# XP-Hardv.net
KiCad netlist of a schematic drawn in Altium Designer
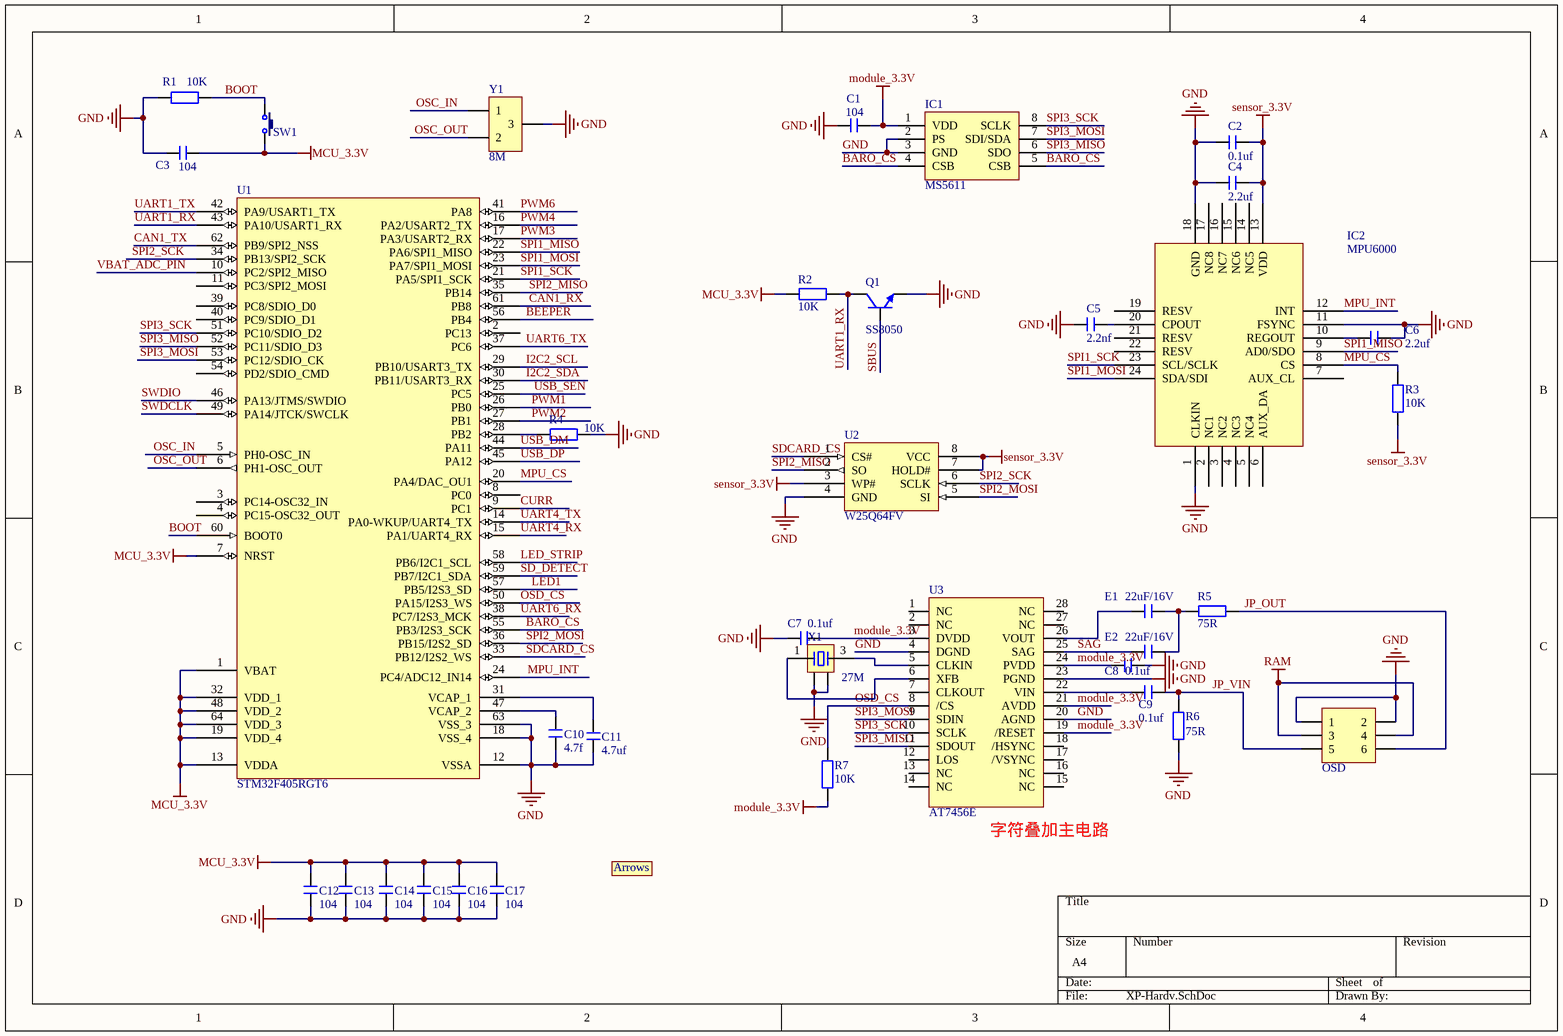
[diagram p0: XP-Hardv.SchDoc]

(export (version "E")
  (design (tool "Eeschema 10.0.6"))
  (components
    (comp (ref "C1")
      (value "104")
      (footprint "C 0402_M")
      (description "无极性贴片电容")
      (fields (field (name "版权归属") "源创客"))
      (libsource (lib "3.1   - 电阻-电容-电感") (part "C"))
    )
    (comp (ref "C2")
      (value "0.1uf")
      (footprint "C 0402_M")
      (description "无极性贴片电容")
      (fields (field (name "版权归属") "源创客"))
      (libsource (lib "3.1   - 电阻-电容-电感") (part "C"))
    )
    (comp (ref "C3")
      (value "104")
      (footprint "C 0402_M")
      (description "无极性贴片电容")
      (fields (field (name "版权归属") "源创客"))
      (libsource (lib "3.1   - 电阻-电容-电感") (part "C"))
    )
    (comp (ref "C4")
      (value "2.2uf")
      (footprint "C 0402_M")
      (description "无极性贴片电容")
      (fields (field (name "版权归属") "源创客"))
      (libsource (lib "3.1   - 电阻-电容-电感") (part "C"))
    )
    (comp (ref "C5")
      (value "2.2nf")
      (footprint "C 0402_M")
      (description "无极性贴片电容")
      (fields (field (name "版权归属") "源创客"))
      (libsource (lib "3.1   - 电阻-电容-电感") (part "C"))
    )
    (comp (ref "C6")
      (value "2.2uf")
      (footprint "C 0402_M")
      (description "无极性贴片电容")
      (fields (field (name "版权归属") "源创客"))
      (libsource (lib "3.1   - 电阻-电容-电感") (part "C"))
    )
    (comp (ref "C7")
      (value "0.1uf")
      (footprint "C 0402_M")
      (description "无极性贴片电容")
      (fields (field (name "版权归属") "源创客"))
      (libsource (lib "3.1   - 电阻-电容-电感") (part "C"))
    )
    (comp (ref "C8")
      (value "0.1uf")
      (footprint "C 0402_M")
      (description "无极性贴片电容")
      (fields (field (name "版权归属") "源创客"))
      (libsource (lib "3.1   - 电阻-电容-电感") (part "C"))
    )
    (comp (ref "C9")
      (value "0.1uf")
      (footprint "C 0402_M")
      (description "无极性贴片电容")
      (fields (field (name "版权归属") "源创客"))
      (libsource (lib "3.1   - 电阻-电容-电感") (part "C"))
    )
    (comp (ref "C10")
      (value "4.7f")
      (footprint "C 0402_M")
      (description "无极性贴片电容")
      (fields (field (name "版权归属") "源创客"))
      (libsource (lib "3.1   - 电阻-电容-电感") (part "C"))
    )
    (comp (ref "C11")
      (value "4.7uf")
      (footprint "C 0402_M")
      (description "无极性贴片电容")
      (fields (field (name "版权归属") "源创客"))
      (libsource (lib "3.1   - 电阻-电容-电感") (part "C"))
    )
    (comp (ref "C12")
      (value "104")
      (footprint "C 0402_M")
      (description "无极性贴片电容")
      (fields (field (name "版权归属") "源创客"))
      (libsource (lib "3.1   - 电阻-电容-电感") (part "C"))
    )
    (comp (ref "C13")
      (value "104")
      (footprint "C 0402_M")
      (description "无极性贴片电容")
      (fields (field (name "版权归属") "源创客"))
      (libsource (lib "3.1   - 电阻-电容-电感") (part "C"))
    )
    (comp (ref "C14")
      (value "104")
      (footprint "C 0402_M")
      (description "无极性贴片电容")
      (fields (field (name "版权归属") "源创客"))
      (libsource (lib "3.1   - 电阻-电容-电感") (part "C"))
    )
    (comp (ref "C15")
      (value "104")
      (footprint "C 0402_M")
      (description "无极性贴片电容")
      (fields (field (name "版权归属") "源创客"))
      (libsource (lib "3.1   - 电阻-电容-电感") (part "C"))
    )
    (comp (ref "C16")
      (value "104")
      (footprint "C 0402_M")
      (description "无极性贴片电容")
      (fields (field (name "版权归属") "源创客"))
      (libsource (lib "3.1   - 电阻-电容-电感") (part "C"))
    )
    (comp (ref "C17")
      (value "104")
      (footprint "C 0402_M")
      (description "无极性贴片电容")
      (fields (field (name "版权归属") "源创客"))
      (libsource (lib "3.1   - 电阻-电容-电感") (part "C"))
    )
    (comp (ref "E1")
      (value "22uF/16V")
      (footprint "C 0805_L")
      (description "无极性贴片电容")
      (fields (field (name "版权归属") "源创客"))
      (libsource (lib "3.1   - 电阻-电容-电感") (part "C"))
    )
    (comp (ref "E2")
      (value "22uF/16V")
      (footprint "C 0805_L")
      (description "无极性贴片电容")
      (fields (field (name "版权归属") "源创客"))
      (libsource (lib "3.1   - 电阻-电容-电感") (part "C"))
    )
    (comp (ref "IC1")
      (value "MS5611")
      (footprint "MS5611")
      (description "气压传感器")
      (fields (field (name "版权归属") "源创客"))
      (libsource (lib "11.1 - 传感元件") (part "MS5611"))
    )
    (comp (ref "IC2")
      (value "MPU6000")
      (footprint "MPU6050")
      (fields (field (name "版权所有") "河池学院智能控制重点实验室"))
      (libsource (lib "传感器件") (part "MPU6000"))
    )
    (comp (ref "logo1")
      (value "Arrows")
      (footprint "Arrows - E")
      (fields (field (name "版权所有") "深圳市哈鸣科技有限公司"))
      (libsource (lib "BETAFPV") (part "Arrows"))
    )
    (comp (ref "OSD")
      (value "Header3X2")
      (footprint "PHD2.0-LI-2x3P")
      (description "3*2P接插件")
      (fields (field (name "版权归属") "源创客"))
      (libsource (lib "4.4   - 接插件-脚距2.0") (part "Header 3X2"))
    )
    (comp (ref "Q1")
      (value "SS8050")
      (footprint "SOT23-3M")
      (description "高频放大-NPN型")
      (fields (field (name "版权归属") "源创客"))
      (libsource (lib "6.2   - 三极管") (part "8050-SMD"))
    )
    (comp (ref "R1")
      (value "10K")
      (footprint "R 0402_M")
      (description "贴片电阻")
      (fields (field (name "版权归属") "源创客"))
      (libsource (lib "3.1   - 电阻-电容-电感") (part "R"))
    )
    (comp (ref "R2")
      (value "10K")
      (footprint "R 0402_M")
      (description "贴片电阻")
      (fields (field (name "版权归属") "源创客"))
      (libsource (lib "3.1   - 电阻-电容-电感") (part "R"))
    )
    (comp (ref "R3")
      (value "10K")
      (footprint "R 0402_M")
      (description "贴片电阻")
      (fields (field (name "版权归属") "源创客"))
      (libsource (lib "3.1   - 电阻-电容-电感") (part "R"))
    )
    (comp (ref "R4")
      (value "10K")
      (footprint "R 0402_M")
      (description "贴片电阻")
      (fields (field (name "版权归属") "源创客"))
      (libsource (lib "3.1   - 电阻-电容-电感") (part "R"))
    )
    (comp (ref "R5")
      (value "75R")
      (footprint "R 0402_M")
      (description "贴片电阻")
      (fields (field (name "版权归属") "源创客"))
      (libsource (lib "3.1   - 电阻-电容-电感") (part "R"))
    )
    (comp (ref "R6")
      (value "75R")
      (footprint "R 0402_M")
      (description "贴片电阻")
      (fields (field (name "版权归属") "源创客"))
      (libsource (lib "3.1   - 电阻-电容-电感") (part "R"))
    )
    (comp (ref "R7")
      (value "10K")
      (footprint "R 0402_M")
      (description "贴片电阻")
      (fields (field (name "版权归属") "源创客"))
      (libsource (lib "3.1   - 电阻-电容-电感") (part "R"))
    )
    (comp (ref "SW1")
      (value "3x6x5")
      (footprint "TSW 3*6*4.3-S-W")
      (description "3x6轻触开关")
      (fields (field (name "版权归属") "源创客"))
      (libsource (lib "5.1   - 按键-开关") (part "TSW 3x6"))
    )
    (comp (ref "U1")
      (value "STM32F405RGT6")
      (footprint "LQFP64 10x10_N")
      (description "32位STM单片机")
      (libsource (lib "2.1   - STM32系列单片机") (part "STM32F405RGT6"))
    )
    (comp (ref "U2")
      (value "W25Q64FV")
      (footprint "Q-WSON8_6x5")
      (description "存储器芯片-64M")
      (libsource (lib "L-存储器芯片") (part "W25Q64FV"))
    )
    (comp (ref "U3")
      (value "AT7456E")
      (footprint "AT7456E - B")
      (fields (field (name "LIBRARY NAME") "字符叠加芯片") (field (name "版权所有") "河池学院智能控制重点实验室"))
      (libsource (lib "L-AT7456E") (part "AT7456E"))
    )
    (comp (ref "X1")
      (value "27M")
      (footprint "OSC 3225-4P")
      (description "4脚无源晶振")
      (fields (field (name "版权归属") "源创客"))
      (libsource (lib "10.1 - 保险丝-晶振") (part "XTAL-4P"))
    )
    (comp (ref "Y1")
      (value "8M")
      (footprint "L - CSTCE-3213")
      (fields (field (name "版权归属") "Ly"))
      (libsource (lib "L-晶振") (part "CSTCE"))
    )
  )
  (nets
    (net (code "1") (name "/BARO_CS") (class "Default")
      (node (ref "IC1") (pin "4") (pinfunction "CSB_4") (pintype "passive"))
      (node (ref "IC1") (pin "5") (pinfunction "CSB_5") (pintype "passive"))
      (node (ref "U1") (pin "55") (pinfunction "PB3/I2S3_SCK_55") (pintype "bidirectional"))
    )
    (net (code "2") (name "/BEEPER") (class "Default")
      (node (ref "U1") (pin "56") (pinfunction "PB4_56") (pintype "bidirectional"))
    )
    (net (code "3") (name "/BOOT") (class "Default")
      (node (ref "R1") (pin "1") (pinfunction "1_1") (pintype "passive"))
      (node (ref "SW1") (pin "1") (pinfunction "1_1") (pintype "passive"))
      (node (ref "U1") (pin "60") (pinfunction "BOOT0_60") (pintype "input"))
    )
    (net (code "4") (name "/CAN1_RX") (class "Default")
      (node (ref "U1") (pin "61") (pinfunction "PB8_61") (pintype "bidirectional"))
    )
    (net (code "5") (name "/CAN1_TX") (class "Default")
      (node (ref "U1") (pin "62") (pinfunction "PB9/SPI2_NSS_62") (pintype "bidirectional"))
    )
    (net (code "6") (name "/CURR") (class "Default")
      (node (ref "U1") (pin "9") (pinfunction "PC1_9") (pintype "bidirectional"))
    )
    (net (code "7") (name "/I2C2_SCL") (class "Default")
      (node (ref "U1") (pin "29") (pinfunction "PB10/USART3_TX_29") (pintype "bidirectional"))
    )
    (net (code "8") (name "/I2C2_SDA") (class "Default")
      (node (ref "U1") (pin "30") (pinfunction "PB11/USART3_RX_30") (pintype "bidirectional"))
    )
    (net (code "9") (name "/JP_OUT") (class "Default")
      (node (ref "OSD") (pin "6") (pinfunction "6_6") (pintype "passive"))
      (node (ref "R5") (pin "2") (pinfunction "2_2") (pintype "passive"))
    )
    (net (code "10") (name "/JP_VIN") (class "Default")
      (node (ref "C9") (pin "2") (pinfunction "2_2") (pintype "passive"))
      (node (ref "OSD") (pin "5") (pinfunction "5_5") (pintype "passive"))
      (node (ref "R6") (pin "2") (pinfunction "2_2") (pintype "passive"))
    )
    (net (code "11") (name "/LED1") (class "Default")
      (node (ref "U1") (pin "57") (pinfunction "PB5/I2S3_SD_57") (pintype "bidirectional"))
    )
    (net (code "12") (name "/LED_STRIP") (class "Default")
      (node (ref "U1") (pin "58") (pinfunction "PB6/I2C1_SCL_58") (pintype "bidirectional"))
    )
    (net (code "13") (name "/MPU_CS") (class "Default")
      (node (ref "IC2") (pin "8") (pinfunction "CS_8") (pintype "passive"))
      (node (ref "R3") (pin "2") (pinfunction "2_2") (pintype "passive"))
      (node (ref "U1") (pin "20") (pinfunction "PA4/DAC_OU1_20") (pintype "bidirectional"))
    )
    (net (code "14") (name "/MPU_INT") (class "Default")
      (node (ref "IC2") (pin "12") (pinfunction "INT_12") (pintype "passive"))
      (node (ref "U1") (pin "24") (pinfunction "PC4/ADC12_IN14_24") (pintype "bidirectional"))
    )
    (net (code "15") (name "/OSC_IN") (class "Default")
      (node (ref "U1") (pin "5") (pinfunction "PH0-OSC_IN_5") (pintype "input"))
      (node (ref "Y1") (pin "1") (pinfunction "1_1") (pintype "passive"))
    )
    (net (code "16") (name "/OSC_OUT") (class "Default")
      (node (ref "U1") (pin "6") (pinfunction "PH1-OSC_OUT_6") (pintype "output"))
      (node (ref "Y1") (pin "2") (pinfunction "2_2") (pintype "passive"))
    )
    (net (code "17") (name "/OSD_CS") (class "Default")
      (node (ref "R7") (pin "2") (pinfunction "2_2") (pintype "passive"))
      (node (ref "U1") (pin "50") (pinfunction "PA15/I2S3_WS_50") (pintype "bidirectional"))
      (node (ref "U3") (pin "8") (pinfunction "/CS_8") (pintype "passive"))
    )
    (net (code "18") (name "/PWM1") (class "Default")
      (node (ref "U1") (pin "26") (pinfunction "PB0_26") (pintype "bidirectional"))
    )
    (net (code "19") (name "/PWM2") (class "Default")
      (node (ref "U1") (pin "27") (pinfunction "PB1_27") (pintype "bidirectional"))
    )
    (net (code "20") (name "/PWM3") (class "Default")
      (node (ref "U1") (pin "17") (pinfunction "PA3/USART2_RX_17") (pintype "bidirectional"))
    )
    (net (code "21") (name "/PWM4") (class "Default")
      (node (ref "U1") (pin "16") (pinfunction "PA2/USART2_TX_16") (pintype "bidirectional"))
    )
    (net (code "22") (name "/PWM6") (class "Default")
      (node (ref "U1") (pin "41") (pinfunction "PA8_41") (pintype "bidirectional"))
    )
    (net (code "23") (name "/SAG") (class "Default")
      (node (ref "E2") (pin "1") (pinfunction "1_1") (pintype "passive"))
      (node (ref "U3") (pin "25") (pinfunction "SAG_25") (pintype "passive"))
    )
    (net (code "24") (name "/SBUS") (class "Default")
      (node (ref "Q1") (pin "1") (pinfunction "B_1") (pintype "passive"))
    )
    (net (code "25") (name "/SDCARD_CS") (class "Default")
      (node (ref "U1") (pin "33") (pinfunction "PB12/I2S2_WS_33") (pintype "bidirectional"))
      (node (ref "U2") (pin "1") (pinfunction "CS#_1") (pintype "input"))
    )
    (net (code "26") (name "/SD_DETECT") (class "Default")
      (node (ref "U1") (pin "59") (pinfunction "PB7/I2C1_SDA_59") (pintype "bidirectional"))
    )
    (net (code "27") (name "/SPI1_MISO") (class "Default")
      (node (ref "IC2") (pin "9") (pinfunction "AD0/SDO_9") (pintype "passive"))
      (node (ref "U1") (pin "22") (pinfunction "PA6/SPI1_MISO_22") (pintype "bidirectional"))
    )
    (net (code "28") (name "/SPI1_MOSI") (class "Default")
      (node (ref "IC2") (pin "24") (pinfunction "SDA/SDI_24") (pintype "passive"))
      (node (ref "U1") (pin "23") (pinfunction "PA7/SPI1_MOSI_23") (pintype "bidirectional"))
    )
    (net (code "29") (name "/SPI1_SCK") (class "Default")
      (node (ref "IC2") (pin "23") (pinfunction "SCL/SCLK_23") (pintype "passive"))
      (node (ref "U1") (pin "21") (pinfunction "PA5/SPI1_SCK_21") (pintype "bidirectional"))
    )
    (net (code "30") (name "/SPI2_MISO") (class "Default")
      (node (ref "U1") (pin "35") (pinfunction "PB14_35") (pintype "bidirectional"))
      (node (ref "U2") (pin "2") (pinfunction "SO_2") (pintype "output"))
    )
    (net (code "31") (name "/SPI2_MOSI") (class "Default")
      (node (ref "U1") (pin "36") (pinfunction "PB15/I2S2_SD_36") (pintype "bidirectional"))
      (node (ref "U2") (pin "5") (pinfunction "SI_5") (pintype "input"))
    )
    (net (code "32") (name "/SPI2_SCK") (class "Default")
      (node (ref "U1") (pin "34") (pinfunction "PB13/SPI2_SCK_34") (pintype "bidirectional"))
      (node (ref "U2") (pin "6") (pinfunction "SCLK_6") (pintype "input"))
    )
    (net (code "33") (name "/SPI3_MISO") (class "Default")
      (node (ref "IC1") (pin "6") (pinfunction "SDO_6") (pintype "passive"))
      (node (ref "U1") (pin "52") (pinfunction "PC11/SDIO_D3_52") (pintype "bidirectional"))
      (node (ref "U3") (pin "11") (pinfunction "SDOUT_11") (pintype "passive"))
    )
    (net (code "34") (name "/SPI3_MOSI") (class "Default")
      (node (ref "IC1") (pin "7") (pinfunction "SDI/SDA_7") (pintype "passive"))
      (node (ref "U1") (pin "53") (pinfunction "PC12/SDIO_CK_53") (pintype "bidirectional"))
      (node (ref "U3") (pin "9") (pinfunction "SDIN_9") (pintype "passive"))
    )
    (net (code "35") (name "/SPI3_SCK") (class "Default")
      (node (ref "IC1") (pin "8") (pinfunction "SCLK_8") (pintype "passive"))
      (node (ref "U1") (pin "51") (pinfunction "PC10/SDIO_D2_51") (pintype "bidirectional"))
      (node (ref "U3") (pin "10") (pinfunction "SCLK_10") (pintype "passive"))
    )
    (net (code "36") (name "/SWDCLK") (class "Default")
      (node (ref "U1") (pin "49") (pinfunction "PA14/JTCK/SWCLK_49") (pintype "bidirectional"))
    )
    (net (code "37") (name "/SWDIO") (class "Default")
      (node (ref "U1") (pin "46") (pinfunction "PA13/JTMS/SWDIO_46") (pintype "bidirectional"))
    )
    (net (code "38") (name "/UART1_RX") (class "Default")
      (node (ref "Q1") (pin "3") (pinfunction "C_3") (pintype "passive"))
      (node (ref "R2") (pin "1") (pinfunction "1_1") (pintype "passive"))
      (node (ref "U1") (pin "43") (pinfunction "PA10/USART1_RX_43") (pintype "bidirectional"))
    )
    (net (code "39") (name "/UART1_TX") (class "Default")
      (node (ref "U1") (pin "42") (pinfunction "PA9/USART1_TX_42") (pintype "bidirectional"))
    )
    (net (code "40") (name "/UART4_RX") (class "Default")
      (node (ref "U1") (pin "15") (pinfunction "PA1/UART4_RX_15") (pintype "bidirectional"))
    )
    (net (code "41") (name "/UART4_TX") (class "Default")
      (node (ref "U1") (pin "14") (pinfunction "PA0-WKUP/UART4_TX_14") (pintype "bidirectional"))
    )
    (net (code "42") (name "/UART6_RX") (class "Default")
      (node (ref "U1") (pin "38") (pinfunction "PC7/I2S3_MCK_38") (pintype "bidirectional"))
    )
    (net (code "43") (name "/UART6_TX") (class "Default")
      (node (ref "U1") (pin "37") (pinfunction "PC6_37") (pintype "bidirectional"))
    )
    (net (code "44") (name "/USB_DM") (class "Default")
      (node (ref "U1") (pin "44") (pinfunction "PA11_44") (pintype "bidirectional"))
    )
    (net (code "45") (name "/USB_DP") (class "Default")
      (node (ref "U1") (pin "45") (pinfunction "PA12_45") (pintype "bidirectional"))
    )
    (net (code "46") (name "/USB_SEN") (class "Default")
      (node (ref "U1") (pin "25") (pinfunction "PC5_25") (pintype "bidirectional"))
    )
    (net (code "47") (name "/VBAT_ADC_PIN") (class "Default")
      (node (ref "U1") (pin "10") (pinfunction "PC2/SPI2_MISO_10") (pintype "bidirectional"))
    )
    (net (code "49") (name "GND") (class "Default")
      (node (ref "C1") (pin "2") (pinfunction "2_2") (pintype "passive"))
      (node (ref "C10") (pin "1") (pinfunction "1_1") (pintype "passive"))
      (node (ref "C11") (pin "1") (pinfunction "1_1") (pintype "passive"))
      (node (ref "C12") (pin "1") (pinfunction "1_1") (pintype "passive"))
      (node (ref "C13") (pin "1") (pinfunction "1_1") (pintype "passive"))
      (node (ref "C14") (pin "1") (pinfunction "1_1") (pintype "passive"))
      (node (ref "C15") (pin "1") (pinfunction "1_1") (pintype "passive"))
      (node (ref "C16") (pin "1") (pinfunction "1_1") (pintype "passive"))
      (node (ref "C17") (pin "1") (pinfunction "1_1") (pintype "passive"))
      (node (ref "C2") (pin "2") (pinfunction "2_2") (pintype "passive"))
      (node (ref "C3") (pin "1") (pinfunction "1_1") (pintype "passive"))
      (node (ref "C4") (pin "2") (pinfunction "2_2") (pintype "passive"))
      (node (ref "C5") (pin "2") (pinfunction "2_2") (pintype "passive"))
      (node (ref "C6") (pin "1") (pinfunction "1_1") (pintype "passive"))
      (node (ref "C7") (pin "1") (pinfunction "1_1") (pintype "passive"))
      (node (ref "C8") (pin "2") (pinfunction "2_2") (pintype "passive"))
      (node (ref "IC1") (pin "2") (pinfunction "PS_2") (pintype "passive"))
      (node (ref "IC1") (pin "3") (pinfunction "GND_3") (pintype "passive"))
      (node (ref "IC2") (pin "1") (pinfunction "CLKIN_1") (pintype "passive"))
      (node (ref "IC2") (pin "11") (pinfunction "FSYNC_11") (pintype "passive"))
      (node (ref "IC2") (pin "18") (pinfunction "GND_18") (pintype "passive"))
      (node (ref "OSD") (pin "1") (pinfunction "1_1") (pintype "passive"))
      (node (ref "OSD") (pin "2") (pinfunction "2_2") (pintype "passive"))
      (node (ref "Q1") (pin "2") (pinfunction "E_2") (pintype "passive"))
      (node (ref "R1") (pin "2") (pinfunction "2_2") (pintype "passive"))
      (node (ref "R4") (pin "2") (pinfunction "2_2") (pintype "passive"))
      (node (ref "R6") (pin "1") (pinfunction "1_1") (pintype "passive"))
      (node (ref "U1") (pin "12") (pinfunction "VSSA_12") (pintype "power_in"))
      (node (ref "U1") (pin "18") (pinfunction "VSS_4_18") (pintype "power_in"))
      (node (ref "U1") (pin "63") (pinfunction "VSS_3_63") (pintype "power_in"))
      (node (ref "U2") (pin "4") (pinfunction "GND_4") (pintype "power_in"))
      (node (ref "U3") (pin "20") (pinfunction "AGND_20") (pintype "passive"))
      (node (ref "U3") (pin "23") (pinfunction "PGND_23") (pintype "passive"))
      (node (ref "U3") (pin "4") (pinfunction "DGND_4") (pintype "passive"))
      (node (ref "X1") (pin "2") (pinfunction "2_2") (pintype "passive"))
      (node (ref "X1") (pin "4") (pinfunction "4_4") (pintype "passive"))
      (node (ref "Y1") (pin "3") (pinfunction "3_3") (pintype "passive"))
    )
    (net (code "50") (name "MCU_3.3V") (class "Default")
      (node (ref "C12") (pin "2") (pinfunction "2_2") (pintype "passive"))
      (node (ref "C13") (pin "2") (pinfunction "2_2") (pintype "passive"))
      (node (ref "C14") (pin "2") (pinfunction "2_2") (pintype "passive"))
      (node (ref "C15") (pin "2") (pinfunction "2_2") (pintype "passive"))
      (node (ref "C16") (pin "2") (pinfunction "2_2") (pintype "passive"))
      (node (ref "C17") (pin "2") (pinfunction "2_2") (pintype "passive"))
      (node (ref "C3") (pin "2") (pinfunction "2_2") (pintype "passive"))
      (node (ref "R2") (pin "2") (pinfunction "2_2") (pintype "passive"))
      (node (ref "SW1") (pin "2") (pinfunction "2_2") (pintype "passive"))
      (node (ref "U1") (pin "1") (pinfunction "VBAT_1") (pintype "power_in"))
      (node (ref "U1") (pin "13") (pinfunction "VDDA_13") (pintype "power_in"))
      (node (ref "U1") (pin "19") (pinfunction "VDD_4_19") (pintype "power_in"))
      (node (ref "U1") (pin "32") (pinfunction "VDD_1_32") (pintype "power_in"))
      (node (ref "U1") (pin "48") (pinfunction "VDD_2_48") (pintype "power_in"))
      (node (ref "U1") (pin "64") (pinfunction "VDD_3_64") (pintype "power_in"))
      (node (ref "U1") (pin "7") (pinfunction "NRST_7") (pintype "bidirectional"))
    )
    (net (code "51") (name "Net-(E1-Pad2)") (class "Default")
      (node (ref "E1") (pin "2") (pinfunction "2_2") (pintype "passive"))
      (node (ref "E2") (pin "2") (pinfunction "2_2") (pintype "passive"))
      (node (ref "R5") (pin "1") (pinfunction "1_1") (pintype "passive"))
    )
    (net (code "52") (name "Net-(IC2-CPOUT)") (class "Default")
      (node (ref "C5") (pin "1") (pinfunction "1_1") (pintype "passive"))
      (node (ref "IC2") (pin "20") (pinfunction "CPOUT_20") (pintype "passive"))
    )
    (net (code "53") (name "Net-(IC2-REGOUT)") (class "Default")
      (node (ref "C6") (pin "2") (pinfunction "2_2") (pintype "passive"))
      (node (ref "IC2") (pin "10") (pinfunction "REGOUT_10") (pintype "passive"))
    )
    (net (code "54") (name "Net-(U1-PB2)") (class "Default")
      (node (ref "R4") (pin "1") (pinfunction "1_1") (pintype "passive"))
      (node (ref "U1") (pin "28") (pinfunction "PB2_28") (pintype "bidirectional"))
    )
    (net (code "55") (name "Net-(U1-VCAP_1)") (class "Default")
      (node (ref "C11") (pin "2") (pinfunction "2_2") (pintype "passive"))
      (node (ref "U1") (pin "31") (pinfunction "VCAP_1_31") (pintype "passive"))
    )
    (net (code "56") (name "Net-(U1-VCAP_2)") (class "Default")
      (node (ref "C10") (pin "2") (pinfunction "2_2") (pintype "passive"))
      (node (ref "U1") (pin "47") (pinfunction "VCAP_2_47") (pintype "passive"))
    )
    (net (code "57") (name "Net-(U3-CLKIN)") (class "Default")
      (node (ref "U3") (pin "5") (pinfunction "CLKIN_5") (pintype "passive"))
      (node (ref "X1") (pin "3") (pinfunction "3_3") (pintype "passive"))
    )
    (net (code "58") (name "Net-(U3-VIN)") (class "Default")
      (node (ref "C9") (pin "1") (pinfunction "1_1") (pintype "passive"))
      (node (ref "U3") (pin "22") (pinfunction "VIN_22") (pintype "passive"))
    )
    (net (code "59") (name "Net-(U3-VOUT)") (class "Default")
      (node (ref "E1") (pin "1") (pinfunction "1_1") (pintype "passive"))
      (node (ref "U3") (pin "26") (pinfunction "VOUT_26") (pintype "passive"))
    )
    (net (code "60") (name "Net-(U3-XFB)") (class "Default")
      (node (ref "U3") (pin "6") (pinfunction "XFB_6") (pintype "passive"))
      (node (ref "X1") (pin "1") (pinfunction "1_1") (pintype "passive"))
    )
    (net (code "61") (name "RAM") (class "Default")
      (node (ref "OSD") (pin "3") (pinfunction "3_3") (pintype "passive"))
      (node (ref "OSD") (pin "4") (pinfunction "4_4") (pintype "passive"))
    )
    (net (code "62") (name "module_3.3V") (class "Default")
      (node (ref "C1") (pin "1") (pinfunction "1_1") (pintype "passive"))
      (node (ref "C7") (pin "2") (pinfunction "2_2") (pintype "passive"))
      (node (ref "C8") (pin "1") (pinfunction "1_1") (pintype "passive"))
      (node (ref "IC1") (pin "1") (pinfunction "VDD_1") (pintype "passive"))
      (node (ref "R7") (pin "1") (pinfunction "1_1") (pintype "passive"))
      (node (ref "U3") (pin "19") (pinfunction "/RESET_19") (pintype "passive"))
      (node (ref "U3") (pin "21") (pinfunction "AVDD_21") (pintype "passive"))
      (node (ref "U3") (pin "24") (pinfunction "PVDD_24") (pintype "passive"))
      (node (ref "U3") (pin "3") (pinfunction "DVDD_3") (pintype "passive"))
    )
    (net (code "63") (name "sensor_3.3V") (class "Default")
      (node (ref "C2") (pin "1") (pinfunction "1_1") (pintype "passive"))
      (node (ref "C4") (pin "1") (pinfunction "1_1") (pintype "passive"))
      (node (ref "IC2") (pin "13") (pinfunction "VDD_13") (pintype "passive"))
      (node (ref "R3") (pin "1") (pinfunction "1_1") (pintype "passive"))
      (node (ref "U2") (pin "3") (pinfunction "WP#_3") (pintype "power_in"))
      (node (ref "U2") (pin "7") (pinfunction "HOLD#_7") (pintype "power_in"))
      (node (ref "U2") (pin "8") (pinfunction "VCC_8") (pintype "power_in"))
    )
    (net (code "64") (name "unconnected-(IC2-AUX_CL-Pad7)") (class "Default")
      (node (ref "IC2") (pin "7") (pinfunction "AUX_CL_7") (pintype "passive"))
    )
    (net (code "65") (name "unconnected-(IC2-AUX_DA-Pad6)") (class "Default")
      (node (ref "IC2") (pin "6") (pinfunction "AUX_DA_6") (pintype "passive"))
    )
    (net (code "66") (name "unconnected-(IC2-NC1-Pad2)") (class "Default")
      (node (ref "IC2") (pin "2") (pinfunction "NC1_2") (pintype "passive"))
    )
    (net (code "67") (name "unconnected-(IC2-NC2-Pad3)") (class "Default")
      (node (ref "IC2") (pin "3") (pinfunction "NC2_3") (pintype "passive"))
    )
    (net (code "68") (name "unconnected-(IC2-NC3-Pad4)") (class "Default")
      (node (ref "IC2") (pin "4") (pinfunction "NC3_4") (pintype "passive"))
    )
    (net (code "69") (name "unconnected-(IC2-NC4-Pad5)") (class "Default")
      (node (ref "IC2") (pin "5") (pinfunction "NC4_5") (pintype "passive"))
    )
    (net (code "70") (name "unconnected-(IC2-NC5-Pad14)") (class "Default")
      (node (ref "IC2") (pin "14") (pinfunction "NC5_14") (pintype "passive"))
    )
    (net (code "71") (name "unconnected-(IC2-NC6-Pad15)") (class "Default")
      (node (ref "IC2") (pin "15") (pinfunction "NC6_15") (pintype "passive"))
    )
    (net (code "72") (name "unconnected-(IC2-NC7-Pad16)") (class "Default")
      (node (ref "IC2") (pin "16") (pinfunction "NC7_16") (pintype "passive"))
    )
    (net (code "73") (name "unconnected-(IC2-NC8-Pad17)") (class "Default")
      (node (ref "IC2") (pin "17") (pinfunction "NC8_17") (pintype "passive"))
    )
    (net (code "74") (name "unconnected-(IC2-RESV-Pad19)") (class "Default")
      (node (ref "IC2") (pin "19") (pinfunction "RESV_19") (pintype "passive"))
    )
    (net (code "75") (name "unconnected-(IC2-RESV-Pad21)") (class "Default")
      (node (ref "IC2") (pin "21") (pinfunction "RESV_21") (pintype "passive"))
    )
    (net (code "76") (name "unconnected-(IC2-RESV-Pad22)") (class "Default")
      (node (ref "IC2") (pin "22") (pinfunction "RESV_22") (pintype "passive"))
    )
    (net (code "77") (name "unconnected-(U1-PC0-Pad8)") (class "Default")
      (node (ref "U1") (pin "8") (pinfunction "PC0_8") (pintype "bidirectional"))
    )
    (net (code "78") (name "unconnected-(U1-PC3{slash}SPI2_MOSI-Pad11)") (class "Default")
      (node (ref "U1") (pin "11") (pinfunction "PC3/SPI2_MOSI_11") (pintype "bidirectional"))
    )
    (net (code "79") (name "unconnected-(U1-PC8{slash}SDIO_D0-Pad39)") (class "Default")
      (node (ref "U1") (pin "39") (pinfunction "PC8/SDIO_D0_39") (pintype "bidirectional"))
    )
    (net (code "80") (name "unconnected-(U1-PC9{slash}SDIO_D1-Pad40)") (class "Default")
      (node (ref "U1") (pin "40") (pinfunction "PC9/SDIO_D1_40") (pintype "bidirectional"))
    )
    (net (code "81") (name "unconnected-(U1-PC13-Pad2)") (class "Default")
      (node (ref "U1") (pin "2") (pinfunction "PC13_2") (pintype "bidirectional"))
    )
    (net (code "82") (name "unconnected-(U1-PC14-OSC32_IN-Pad3)") (class "Default")
      (node (ref "U1") (pin "3") (pinfunction "PC14-OSC32_IN_3") (pintype "bidirectional"))
    )
    (net (code "83") (name "unconnected-(U1-PC15-OSC32_OUT-Pad4)") (class "Default")
      (node (ref "U1") (pin "4") (pinfunction "PC15-OSC32_OUT_4") (pintype "bidirectional"))
    )
    (net (code "84") (name "unconnected-(U1-PD2{slash}SDIO_CMD-Pad54)") (class "Default")
      (node (ref "U1") (pin "54") (pinfunction "PD2/SDIO_CMD_54") (pintype "bidirectional"))
    )
    (net (code "85") (name "unconnected-(U3-CLKOUT-Pad7)") (class "Default")
      (node (ref "U3") (pin "7") (pinfunction "CLKOUT_7") (pintype "passive"))
    )
    (net (code "86") (name "unconnected-(U3-LOS-Pad12)") (class "Default")
      (node (ref "U3") (pin "12") (pinfunction "LOS_12") (pintype "passive"))
    )
    (net (code "87") (name "unconnected-(U3-NC-Pad1)") (class "Default")
      (node (ref "U3") (pin "1") (pinfunction "NC_1") (pintype "passive"))
    )
    (net (code "88") (name "unconnected-(U3-NC-Pad2)") (class "Default")
      (node (ref "U3") (pin "2") (pinfunction "NC_2") (pintype "passive"))
    )
    (net (code "89") (name "unconnected-(U3-NC-Pad13)") (class "Default")
      (node (ref "U3") (pin "13") (pinfunction "NC_13") (pintype "passive"))
    )
    (net (code "90") (name "unconnected-(U3-NC-Pad14)") (class "Default")
      (node (ref "U3") (pin "14") (pinfunction "NC_14") (pintype "passive"))
    )
    (net (code "91") (name "unconnected-(U3-NC-Pad15)") (class "Default")
      (node (ref "U3") (pin "15") (pinfunction "NC_15") (pintype "passive"))
    )
    (net (code "92") (name "unconnected-(U3-NC-Pad16)") (class "Default")
      (node (ref "U3") (pin "16") (pinfunction "NC_16") (pintype "passive"))
    )
    (net (code "93") (name "unconnected-(U3-NC-Pad27)") (class "Default")
      (node (ref "U3") (pin "27") (pinfunction "NC_27") (pintype "passive"))
    )
    (net (code "94") (name "unconnected-(U3-NC-Pad28)") (class "Default")
      (node (ref "U3") (pin "28") (pinfunction "NC_28") (pintype "passive"))
    )
    (net (code "95") (name "unconnected-(U3-{slash}HSYNC-Pad18)") (class "Default")
      (node (ref "U3") (pin "18") (pinfunction "/HSYNC_18") (pintype "passive"))
    )
    (net (code "96") (name "unconnected-(U3-{slash}VSYNC-Pad17)") (class "Default")
      (node (ref "U3") (pin "17") (pinfunction "/VSYNC_17") (pintype "passive"))
    )
  )
)
